# BARRERA.net
KiCad netlist of a schematic drawn in EAGLE
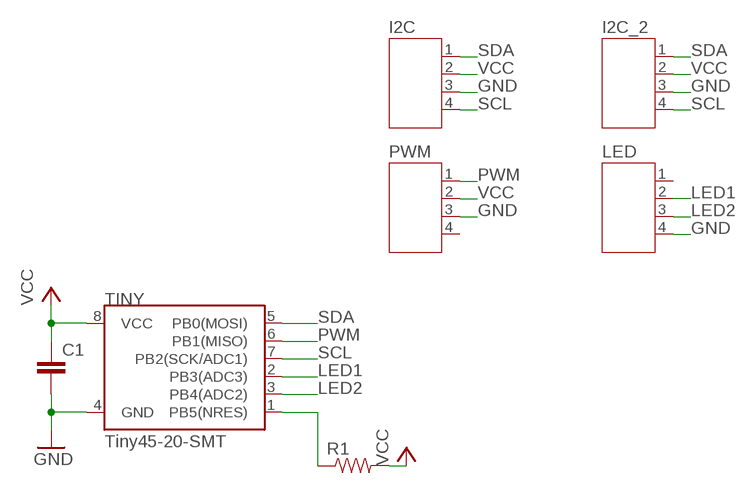
[diagram p0: schematic, sheet 1]

(export (version "E")
  (design (tool "Eeschema 10.0.6"))
  (components
    (comp (ref "C1")
      (value "CAP0603-CAP")
      (footprint "eagle-import:0603-CAP")
      (libsource (lib "eagle-import") (part "CAP0603-CAP"))
    )
    (comp (ref "I2C")
      (value "JST-PH4")
      (footprint "eagle-import:JST-PH4")
      (libsource (lib "eagle-import") (part "JST-PH4"))
    )
    (comp (ref "I2C_2")
      (value "JST-PH4")
      (footprint "eagle-import:JST-PH4")
      (libsource (lib "eagle-import") (part "JST-PH4"))
    )
    (comp (ref "LED")
      (value "JST-PH4")
      (footprint "eagle-import:JST-PH4")
      (libsource (lib "eagle-import") (part "JST-PH4"))
    )
    (comp (ref "PWM")
      (value "JST-PH4")
      (footprint "eagle-import:JST-PH4")
      (libsource (lib "eagle-import") (part "JST-PH4"))
    )
    (comp (ref "R1")
      (value "RESISTOR0603")
      (footprint "eagle-import:0603-RES")
      (libsource (lib "eagle-import") (part "RESISTOR0603"))
    )
    (comp (ref "TINY")
      (value "Tiny45-20-SMT")
      (footprint "eagle-import:SO08-EIAJ")
      (libsource (lib "eagle-import") (part "ATTINY45TINY45-20-SMT"))
    )
  )
  (nets
    (net (code "1") (name "/LED1") (class "Default")
      (node (ref "LED") (pin "2") (pinfunction "2_2") (pintype "passive"))
      (node (ref "TINY") (pin "2") (pinfunction "PB3(ADC3)_2") (pintype "bidirectional"))
    )
    (net (code "2") (name "/LED2") (class "Default")
      (node (ref "LED") (pin "3") (pinfunction "3_3") (pintype "passive"))
      (node (ref "TINY") (pin "3") (pinfunction "PB4(ADC2)_3") (pintype "bidirectional"))
    )
    (net (code "3") (name "/PWM") (class "Default")
      (node (ref "PWM") (pin "1") (pinfunction "1_1") (pintype "passive"))
      (node (ref "TINY") (pin "6") (pinfunction "PB1(MISO)_6") (pintype "bidirectional"))
    )
    (net (code "4") (name "/SCL") (class "Default")
      (node (ref "I2C") (pin "4") (pinfunction "4_4") (pintype "passive"))
      (node (ref "I2C_2") (pin "4") (pinfunction "4_4") (pintype "passive"))
      (node (ref "TINY") (pin "7") (pinfunction "PB2(SCK/ADC1)_7") (pintype "bidirectional"))
    )
    (net (code "5") (name "/SDA") (class "Default")
      (node (ref "I2C") (pin "1") (pinfunction "1_1") (pintype "passive"))
      (node (ref "I2C_2") (pin "1") (pinfunction "1_1") (pintype "passive"))
      (node (ref "TINY") (pin "5") (pinfunction "PB0(MOSI)_5") (pintype "bidirectional"))
    )
    (net (code "6") (name "GND") (class "Default")
      (node (ref "C1") (pin "2") (pinfunction "2_2") (pintype "passive"))
      (node (ref "I2C") (pin "3") (pinfunction "3_3") (pintype "passive"))
      (node (ref "I2C_2") (pin "3") (pinfunction "3_3") (pintype "passive"))
      (node (ref "LED") (pin "4") (pinfunction "4_4") (pintype "passive"))
      (node (ref "PWM") (pin "3") (pinfunction "3_3") (pintype "passive"))
      (node (ref "TINY") (pin "4") (pinfunction "GND_4") (pintype "bidirectional"))
    )
    (net (code "7") (name "Net-(TINY-PB5(NRES))") (class "Default")
      (node (ref "R1") (pin "1") (pinfunction "1_1") (pintype "passive"))
      (node (ref "TINY") (pin "1") (pinfunction "PB5(NRES)_1") (pintype "bidirectional"))
    )
    (net (code "8") (name "VCC") (class "Default")
      (node (ref "C1") (pin "1") (pinfunction "1_1") (pintype "passive"))
      (node (ref "I2C") (pin "2") (pinfunction "2_2") (pintype "passive"))
      (node (ref "I2C_2") (pin "2") (pinfunction "2_2") (pintype "passive"))
      (node (ref "PWM") (pin "2") (pinfunction "2_2") (pintype "passive"))
      (node (ref "R1") (pin "2") (pinfunction "2_2") (pintype "passive"))
      (node (ref "TINY") (pin "8") (pinfunction "VCC_8") (pintype "bidirectional"))
    )
    (net (code "9") (name "unconnected-(LED-Pad1)") (class "Default")
      (node (ref "LED") (pin "1") (pinfunction "1_1") (pintype "passive"))
    )
    (net (code "10") (name "unconnected-(PWM-Pad4)") (class "Default")
      (node (ref "PWM") (pin "4") (pinfunction "4_4") (pintype "passive"))
    )
  )
)
